# BrickPi_1_6.net
KiCad netlist of a schematic drawn in EAGLE
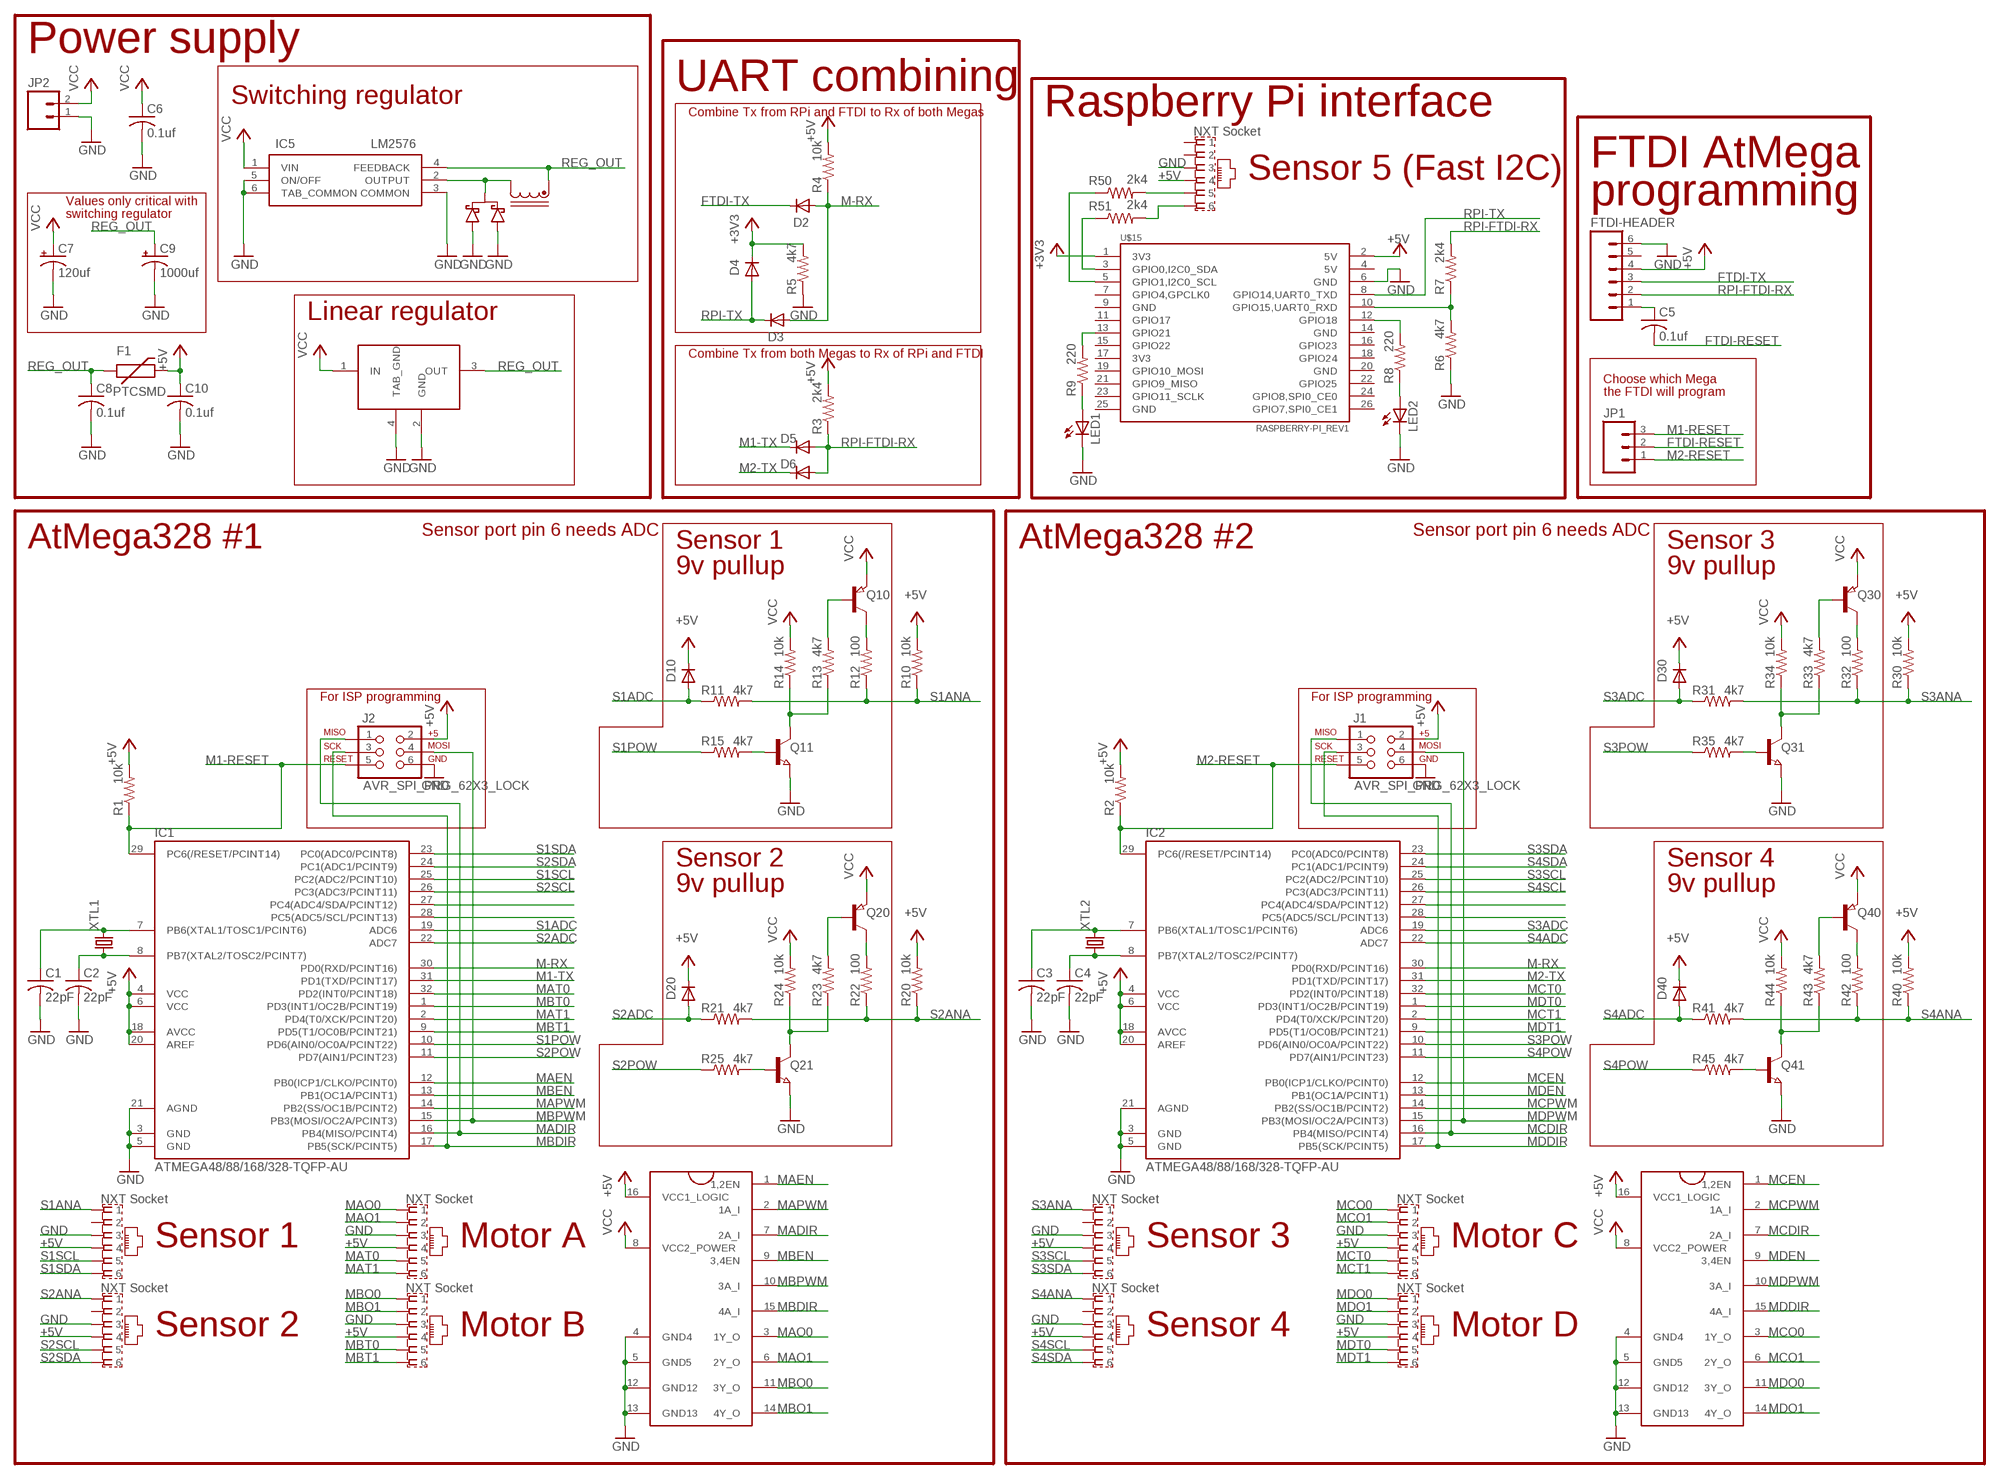
[diagram p0: schematic, sheet 1]

(export (version "E")
  (design (tool "Eeschema 10.0.6"))
  (components
    (comp (ref "C1")
      (value "22pF")
      (footprint "eagle-import:C0805")
      (libsource (lib "eagle-import") (part "C-USC0805"))
    )
    (comp (ref "C2")
      (value "22pF")
      (footprint "eagle-import:C0805")
      (libsource (lib "eagle-import") (part "C-USC0805"))
    )
    (comp (ref "C3")
      (value "22pF")
      (footprint "eagle-import:C0805")
      (libsource (lib "eagle-import") (part "C-USC0805"))
    )
    (comp (ref "C4")
      (value "22pF")
      (footprint "eagle-import:C0805")
      (libsource (lib "eagle-import") (part "C-USC0805"))
    )
    (comp (ref "C5")
      (value "0.1uf")
      (footprint "eagle-import:C0805")
      (libsource (lib "eagle-import") (part "C-USC0805"))
    )
    (comp (ref "C6")
      (value "0.1uf")
      (footprint "eagle-import:C0805")
      (libsource (lib "eagle-import") (part "C-USC0805"))
    )
    (comp (ref "C7")
      (value "120uf")
      (footprint "eagle-import:E2,5-6")
      (libsource (lib "eagle-import") (part "CPOL-USE2.5-6"))
    )
    (comp (ref "C8")
      (value "0.1uf")
      (footprint "eagle-import:C0805")
      (libsource (lib "eagle-import") (part "C-USC0805"))
    )
    (comp (ref "C9")
      (value "1000uf")
      (footprint "eagle-import:E3,5-10")
      (libsource (lib "eagle-import") (part "CPOL-USE3.5-10"))
    )
    (comp (ref "C10")
      (value "0.1uf")
      (footprint "eagle-import:C0805")
      (libsource (lib "eagle-import") (part "C-USC0805"))
    )
    (comp (ref "D1")
      (value "DIODE_SCHOTTKY_VS-6CWQ04FNTRPBF")
      (footprint "eagle-import:DPAK")
      (libsource (lib "eagle-import") (part "DIODE_SCHOTTKY_VS-6CWQ04FNTRPBF"))
    )
    (comp (ref "D2")
      (value "DIODE-SOD80C")
      (footprint "eagle-import:SOD80C")
      (libsource (lib "eagle-import") (part "DIODE-SOD80C"))
    )
    (comp (ref "D3")
      (value "DIODE-SOD80C")
      (footprint "eagle-import:SOD80C")
      (libsource (lib "eagle-import") (part "DIODE-SOD80C"))
    )
    (comp (ref "D4")
      (value "DIODE-SOD80C")
      (footprint "eagle-import:SOD80C")
      (libsource (lib "eagle-import") (part "DIODE-SOD80C"))
    )
    (comp (ref "D5")
      (value "DIODE-SOD80C")
      (footprint "eagle-import:SOD80C")
      (libsource (lib "eagle-import") (part "DIODE-SOD80C"))
    )
    (comp (ref "D6")
      (value "DIODE-SOD80C")
      (footprint "eagle-import:SOD80C")
      (libsource (lib "eagle-import") (part "DIODE-SOD80C"))
    )
    (comp (ref "D10")
      (value "DIODE-SOD80C")
      (footprint "eagle-import:SOD80C")
      (libsource (lib "eagle-import") (part "DIODE-SOD80C"))
    )
    (comp (ref "D20")
      (value "DIODE-SOD80C")
      (footprint "eagle-import:SOD80C")
      (libsource (lib "eagle-import") (part "DIODE-SOD80C"))
    )
    (comp (ref "D30")
      (value "DIODE-SOD80C")
      (footprint "eagle-import:SOD80C")
      (libsource (lib "eagle-import") (part "DIODE-SOD80C"))
    )
    (comp (ref "D40")
      (value "DIODE-SOD80C")
      (footprint "eagle-import:SOD80C")
      (libsource (lib "eagle-import") (part "DIODE-SOD80C"))
    )
    (comp (ref "F1")
      (value "PTCSMD")
      (footprint "eagle-import:PTC-1206")
      (libsource (lib "eagle-import") (part "PTCSMD"))
    )
    (comp (ref "FTDI-HEADER")
      (value "M06LOCK")
      (footprint "eagle-import:1X06_LOCK")
      (libsource (lib "eagle-import") (part "M06LOCK"))
    )
    (comp (ref "IC1")
      (value "ATMEGA48/88/168/328-TQFP-AU")
      (footprint "eagle-import:TQFP32-08")
      (libsource (lib "eagle-import") (part "ATMEGA48/88/168/328-TQFP-AU"))
    )
    (comp (ref "IC2")
      (value "ATMEGA48/88/168/328-TQFP-AU")
      (footprint "eagle-import:TQFP32-08")
      (libsource (lib "eagle-import") (part "ATMEGA48/88/168/328-TQFP-AU"))
    )
    (comp (ref "IC3")
      (value "SN754410")
      (footprint "eagle-import:DIL16-ROUND-HEAT_DIS_SN754410")
      (libsource (lib "eagle-import") (part "SN754410"))
    )
    (comp (ref "IC4")
      (value "SN754410")
      (footprint "eagle-import:DIL16-ROUND-HEAT_DIS_SN754410")
      (libsource (lib "eagle-import") (part "SN754410"))
    )
    (comp (ref "IC5")
      (value "LM2576")
      (footprint "eagle-import:TO220-5-H")
      (libsource (lib "eagle-import") (part "REGULATOR_SWITCHING_LM2575_LM2576"))
    )
    (comp (ref "IC6")
      (value "REGULATOR_5V_TO220-H_7805")
      (footprint "eagle-import:TO220-H")
      (libsource (lib "eagle-import") (part "REGULATOR_5V_TO220-H_7805"))
    )
    (comp (ref "J1")
      (value "AVR_SPI_PRG_62X3_LOCK")
      (footprint "eagle-import:2X3_LOCK")
      (libsource (lib "eagle-import") (part "AVR_SPI_PRG_62X3_LOCK"))
    )
    (comp (ref "J2")
      (value "AVR_SPI_PRG_62X3_LOCK")
      (footprint "eagle-import:2X3_LOCK")
      (libsource (lib "eagle-import") (part "AVR_SPI_PRG_62X3_LOCK"))
    )
    (comp (ref "JP1")
      (value "M03LOCK")
      (footprint "eagle-import:1X03_LOCK")
      (libsource (lib "eagle-import") (part "M03LOCK"))
    )
    (comp (ref "JP2")
      (value "M02LOCK")
      (footprint "eagle-import:1X02_LOCK")
      (libsource (lib "eagle-import") (part "M02LOCK"))
    )
    (comp (ref "LED1")
      (value "LED1206")
      (footprint "eagle-import:LED-1206")
      (libsource (lib "eagle-import") (part "LED1206"))
    )
    (comp (ref "LED2")
      (value "LED1206")
      (footprint "eagle-import:LED-1206")
      (libsource (lib "eagle-import") (part "LED1206"))
    )
    (comp (ref "Q10")
      (value "PNP-TRANSISTOR_SOT23")
      (footprint "eagle-import:SOT23")
      (libsource (lib "eagle-import") (part "PNP-TRANSISTOR_SOT23"))
    )
    (comp (ref "Q11")
      (value "NPN-TRANSISTOR_SOT23")
      (footprint "eagle-import:SOT23")
      (libsource (lib "eagle-import") (part "NPN-TRANSISTOR_SOT23"))
    )
    (comp (ref "Q20")
      (value "PNP-TRANSISTOR_SOT23")
      (footprint "eagle-import:SOT23")
      (libsource (lib "eagle-import") (part "PNP-TRANSISTOR_SOT23"))
    )
    (comp (ref "Q21")
      (value "NPN-TRANSISTOR_SOT23")
      (footprint "eagle-import:SOT23")
      (libsource (lib "eagle-import") (part "NPN-TRANSISTOR_SOT23"))
    )
    (comp (ref "Q30")
      (value "PNP-TRANSISTOR_SOT23")
      (footprint "eagle-import:SOT23")
      (libsource (lib "eagle-import") (part "PNP-TRANSISTOR_SOT23"))
    )
    (comp (ref "Q31")
      (value "NPN-TRANSISTOR_SOT23")
      (footprint "eagle-import:SOT23")
      (libsource (lib "eagle-import") (part "NPN-TRANSISTOR_SOT23"))
    )
    (comp (ref "Q40")
      (value "PNP-TRANSISTOR_SOT23")
      (footprint "eagle-import:SOT23")
      (libsource (lib "eagle-import") (part "PNP-TRANSISTOR_SOT23"))
    )
    (comp (ref "Q41")
      (value "NPN-TRANSISTOR_SOT23")
      (footprint "eagle-import:SOT23")
      (libsource (lib "eagle-import") (part "NPN-TRANSISTOR_SOT23"))
    )
    (comp (ref "R1")
      (value "10k")
      (footprint "eagle-import:0603")
      (libsource (lib "eagle-import") (part "RESISTOR0603-RES"))
    )
    (comp (ref "R2")
      (value "10k")
      (footprint "eagle-import:0603")
      (libsource (lib "eagle-import") (part "RESISTOR0603-RES"))
    )
    (comp (ref "R3")
      (value "2k4")
      (footprint "eagle-import:0603")
      (libsource (lib "eagle-import") (part "RESISTOR0603-RES"))
    )
    (comp (ref "R4")
      (value "10k")
      (footprint "eagle-import:0603")
      (libsource (lib "eagle-import") (part "RESISTOR0603-RES"))
    )
    (comp (ref "R5")
      (value "4k7")
      (footprint "eagle-import:0603")
      (libsource (lib "eagle-import") (part "RESISTOR0603-RES"))
    )
    (comp (ref "R6")
      (value "4k7")
      (footprint "eagle-import:0603")
      (libsource (lib "eagle-import") (part "RESISTOR0603-RES"))
    )
    (comp (ref "R7")
      (value "2k4")
      (footprint "eagle-import:0603")
      (libsource (lib "eagle-import") (part "RESISTOR0603-RES"))
    )
    (comp (ref "R8")
      (value "220")
      (footprint "eagle-import:0603")
      (libsource (lib "eagle-import") (part "RESISTOR0603-RES"))
    )
    (comp (ref "R9")
      (value "220")
      (footprint "eagle-import:0603")
      (libsource (lib "eagle-import") (part "RESISTOR0603-RES"))
    )
    (comp (ref "R10")
      (value "10k")
      (footprint "eagle-import:0603")
      (libsource (lib "eagle-import") (part "RESISTOR0603-RES"))
    )
    (comp (ref "R11")
      (value "4k7")
      (footprint "eagle-import:0603")
      (libsource (lib "eagle-import") (part "RESISTOR0603-RES"))
    )
    (comp (ref "R12")
      (value "100")
      (footprint "eagle-import:0805")
      (libsource (lib "eagle-import") (part "RESISTOR0805-RES"))
    )
    (comp (ref "R13")
      (value "4k7")
      (footprint "eagle-import:0603")
      (libsource (lib "eagle-import") (part "RESISTOR0603-RES"))
    )
    (comp (ref "R14")
      (value "10k")
      (footprint "eagle-import:0603")
      (libsource (lib "eagle-import") (part "RESISTOR0603-RES"))
    )
    (comp (ref "R15")
      (value "4k7")
      (footprint "eagle-import:0603")
      (libsource (lib "eagle-import") (part "RESISTOR0603-RES"))
    )
    (comp (ref "R20")
      (value "10k")
      (footprint "eagle-import:0603")
      (libsource (lib "eagle-import") (part "RESISTOR0603-RES"))
    )
    (comp (ref "R21")
      (value "4k7")
      (footprint "eagle-import:0603")
      (libsource (lib "eagle-import") (part "RESISTOR0603-RES"))
    )
    (comp (ref "R22")
      (value "100")
      (footprint "eagle-import:0805")
      (libsource (lib "eagle-import") (part "RESISTOR0805-RES"))
    )
    (comp (ref "R23")
      (value "4k7")
      (footprint "eagle-import:0603")
      (libsource (lib "eagle-import") (part "RESISTOR0603-RES"))
    )
    (comp (ref "R24")
      (value "10k")
      (footprint "eagle-import:0603")
      (libsource (lib "eagle-import") (part "RESISTOR0603-RES"))
    )
    (comp (ref "R25")
      (value "4k7")
      (footprint "eagle-import:0603")
      (libsource (lib "eagle-import") (part "RESISTOR0603-RES"))
    )
    (comp (ref "R30")
      (value "10k")
      (footprint "eagle-import:0603")
      (libsource (lib "eagle-import") (part "RESISTOR0603-RES"))
    )
    (comp (ref "R31")
      (value "4k7")
      (footprint "eagle-import:0603")
      (libsource (lib "eagle-import") (part "RESISTOR0603-RES"))
    )
    (comp (ref "R32")
      (value "100")
      (footprint "eagle-import:0805")
      (libsource (lib "eagle-import") (part "RESISTOR0805-RES"))
    )
    (comp (ref "R33")
      (value "4k7")
      (footprint "eagle-import:0603")
      (libsource (lib "eagle-import") (part "RESISTOR0603-RES"))
    )
    (comp (ref "R34")
      (value "10k")
      (footprint "eagle-import:0603")
      (libsource (lib "eagle-import") (part "RESISTOR0603-RES"))
    )
    (comp (ref "R35")
      (value "4k7")
      (footprint "eagle-import:0603")
      (libsource (lib "eagle-import") (part "RESISTOR0603-RES"))
    )
    (comp (ref "R40")
      (value "10k")
      (footprint "eagle-import:0603")
      (libsource (lib "eagle-import") (part "RESISTOR0603-RES"))
    )
    (comp (ref "R41")
      (value "4k7")
      (footprint "eagle-import:0603")
      (libsource (lib "eagle-import") (part "RESISTOR0603-RES"))
    )
    (comp (ref "R42")
      (value "100")
      (footprint "eagle-import:0805")
      (libsource (lib "eagle-import") (part "RESISTOR0805-RES"))
    )
    (comp (ref "R43")
      (value "4k7")
      (footprint "eagle-import:0603")
      (libsource (lib "eagle-import") (part "RESISTOR0603-RES"))
    )
    (comp (ref "R44")
      (value "10k")
      (footprint "eagle-import:0603")
      (libsource (lib "eagle-import") (part "RESISTOR0603-RES"))
    )
    (comp (ref "R45")
      (value "4k7")
      (footprint "eagle-import:0603")
      (libsource (lib "eagle-import") (part "RESISTOR0603-RES"))
    )
    (comp (ref "R50")
      (value "2k4")
      (footprint "eagle-import:0603")
      (libsource (lib "eagle-import") (part "RESISTOR0603-RES"))
    )
    (comp (ref "R51")
      (value "2k4")
      (footprint "eagle-import:0603")
      (libsource (lib "eagle-import") (part "RESISTOR0603-RES"))
    )
    (comp (ref "U$3")
      (value "NXT-SOCKETREGULAR")
      (footprint "eagle-import:NXT-SOCKET")
      (libsource (lib "eagle-import") (part "NXT-SOCKETREGULAR"))
    )
    (comp (ref "U$4")
      (value "NXT-SOCKETREGULAR")
      (footprint "eagle-import:NXT-SOCKET")
      (libsource (lib "eagle-import") (part "NXT-SOCKETREGULAR"))
    )
    (comp (ref "U$5")
      (value "NXT-SOCKETREGULAR")
      (footprint "eagle-import:NXT-SOCKET")
      (libsource (lib "eagle-import") (part "NXT-SOCKETREGULAR"))
    )
    (comp (ref "U$7")
      (value "NXT-SOCKETREGULAR")
      (footprint "eagle-import:NXT-SOCKET")
      (libsource (lib "eagle-import") (part "NXT-SOCKETREGULAR"))
    )
    (comp (ref "U$8")
      (value "NXT-SOCKETREGULAR")
      (footprint "eagle-import:NXT-SOCKET")
      (libsource (lib "eagle-import") (part "NXT-SOCKETREGULAR"))
    )
    (comp (ref "U$9")
      (value "NXT-SOCKETREGULAR")
      (footprint "eagle-import:NXT-SOCKET")
      (libsource (lib "eagle-import") (part "NXT-SOCKETREGULAR"))
    )
    (comp (ref "U$10")
      (value "NXT-SOCKETREGULAR")
      (footprint "eagle-import:NXT-SOCKET")
      (libsource (lib "eagle-import") (part "NXT-SOCKETREGULAR"))
    )
    (comp (ref "U$11")
      (value "NXT-SOCKETREGULAR")
      (footprint "eagle-import:NXT-SOCKET")
      (libsource (lib "eagle-import") (part "NXT-SOCKETREGULAR"))
    )
    (comp (ref "U$12")
      (value "NXT-SOCKETREGULAR")
      (footprint "eagle-import:NXT-SOCKET")
      (libsource (lib "eagle-import") (part "NXT-SOCKETREGULAR"))
    )
    (comp (ref "U$14")
      (value "INDUCTOR_PULSE_P0250.XXXNL")
      (footprint "eagle-import:INDUCTOR_PULSE_P0250.XXXNL")
      (libsource (lib "eagle-import") (part "INDUCTOR_PULSE_P0250.XXXNL"))
    )
    (comp (ref "U$15")
      (value "RASPBERRY-PI_REV1")
      (footprint "eagle-import:RASPBERRY-PI_REV1")
      (libsource (lib "eagle-import") (part "RASPBERRY-PI_REV1"))
    )
    (comp (ref "XTL1")
      (value "CRYSTALHC49S")
      (footprint "eagle-import:HC49_S")
      (libsource (lib "eagle-import") (part "CRYSTALHC49S"))
    )
    (comp (ref "XTL2")
      (value "CRYSTALHC49S")
      (footprint "eagle-import:HC49_S")
      (libsource (lib "eagle-import") (part "CRYSTALHC49S"))
    )
  )
  (nets
    (net (code "1") (name "+3V3") (class "Default")
      (node (ref "D4") (pin "C") (pinfunction "C_C") (pintype "passive"))
      (node (ref "R5") (pin "2") (pinfunction "2_2") (pintype "passive"))
      (node (ref "U$15") (pin "1") (pinfunction "3V3_1") (pintype "bidirectional"))
    )
    (net (code "2") (name "+5V") (class "Default")
      (node (ref "C10") (pin "1") (pinfunction "1_1") (pintype "passive"))
      (node (ref "D10") (pin "C") (pinfunction "C_C") (pintype "passive"))
      (node (ref "D20") (pin "C") (pinfunction "C_C") (pintype "passive"))
      (node (ref "D30") (pin "C") (pinfunction "C_C") (pintype "passive"))
      (node (ref "D40") (pin "C") (pinfunction "C_C") (pintype "passive"))
      (node (ref "F1") (pin "2") (pinfunction "2_2") (pintype "bidirectional"))
      (node (ref "FTDI-HEADER") (pin "4") (pinfunction "4_4") (pintype "passive"))
      (node (ref "IC1") (pin "18") (pinfunction "AVCC_18") (pintype "passive"))
      (node (ref "IC1") (pin "20") (pinfunction "AREF_20") (pintype "passive"))
      (node (ref "IC1") (pin "4") (pinfunction "VCC_4") (pintype "power_in"))
      (node (ref "IC1") (pin "6") (pinfunction "VCC_6") (pintype "power_in"))
      (node (ref "IC2") (pin "18") (pinfunction "AVCC_18") (pintype "passive"))
      (node (ref "IC2") (pin "20") (pinfunction "AREF_20") (pintype "passive"))
      (node (ref "IC2") (pin "4") (pinfunction "VCC_4") (pintype "power_in"))
      (node (ref "IC2") (pin "6") (pinfunction "VCC_6") (pintype "power_in"))
      (node (ref "IC3") (pin "16") (pinfunction "VCC1_LOGIC_16") (pintype "bidirectional"))
      (node (ref "IC4") (pin "16") (pinfunction "VCC1_LOGIC_16") (pintype "bidirectional"))
      (node (ref "J1") (pin "2") (pinfunction "2_2") (pintype "passive"))
      (node (ref "J2") (pin "2") (pinfunction "2_2") (pintype "passive"))
      (node (ref "R1") (pin "2") (pinfunction "2_2") (pintype "passive"))
      (node (ref "R10") (pin "2") (pinfunction "2_2") (pintype "passive"))
      (node (ref "R2") (pin "2") (pinfunction "2_2") (pintype "passive"))
      (node (ref "R20") (pin "2") (pinfunction "2_2") (pintype "passive"))
      (node (ref "R3") (pin "2") (pinfunction "2_2") (pintype "passive"))
      (node (ref "R30") (pin "2") (pinfunction "2_2") (pintype "passive"))
      (node (ref "R4") (pin "2") (pinfunction "2_2") (pintype "passive"))
      (node (ref "R40") (pin "2") (pinfunction "2_2") (pintype "passive"))
      (node (ref "U$10") (pin "4") (pinfunction "4_4") (pintype "passive"))
      (node (ref "U$11") (pin "4") (pinfunction "4_4") (pintype "passive"))
      (node (ref "U$12") (pin "4") (pinfunction "4_4") (pintype "passive"))
      (node (ref "U$15") (pin "2") (pinfunction "5V_2") (pintype "bidirectional"))
      (node (ref "U$3") (pin "4") (pinfunction "4_4") (pintype "passive"))
      (node (ref "U$4") (pin "4") (pinfunction "4_4") (pintype "passive"))
      (node (ref "U$5") (pin "4") (pinfunction "4_4") (pintype "passive"))
      (node (ref "U$7") (pin "4") (pinfunction "4_4") (pintype "passive"))
      (node (ref "U$8") (pin "4") (pinfunction "4_4") (pintype "passive"))
      (node (ref "U$9") (pin "4") (pinfunction "4_4") (pintype "passive"))
    )
    (net (code "3") (name "/FTDI-RESET") (class "Default")
      (node (ref "C5") (pin "2") (pinfunction "2_2") (pintype "passive"))
      (node (ref "JP1") (pin "2") (pinfunction "2_2") (pintype "passive"))
    )
    (net (code "4") (name "/FTDI-TX") (class "Default")
      (node (ref "D2") (pin "C") (pinfunction "C_C") (pintype "passive"))
      (node (ref "FTDI-HEADER") (pin "3") (pinfunction "3_3") (pintype "passive"))
    )
    (net (code "5") (name "/M-RX") (class "Default")
      (node (ref "D2") (pin "A") (pinfunction "A_A") (pintype "passive"))
      (node (ref "D3") (pin "A") (pinfunction "A_A") (pintype "passive"))
      (node (ref "IC1") (pin "30") (pinfunction "PD0(RXD/PCINT16)_30") (pintype "bidirectional"))
      (node (ref "IC2") (pin "30") (pinfunction "PD0(RXD/PCINT16)_30") (pintype "bidirectional"))
      (node (ref "R4") (pin "1") (pinfunction "1_1") (pintype "passive"))
    )
    (net (code "6") (name "/M1-RESET") (class "Default")
      (node (ref "IC1") (pin "29") (pinfunction "PC6(/RESET/PCINT14)_29") (pintype "bidirectional"))
      (node (ref "J2") (pin "5") (pinfunction "5_5") (pintype "passive"))
      (node (ref "JP1") (pin "3") (pinfunction "3_3") (pintype "passive"))
      (node (ref "R1") (pin "1") (pinfunction "1_1") (pintype "passive"))
    )
    (net (code "7") (name "/M1-TX") (class "Default")
      (node (ref "D5") (pin "C") (pinfunction "C_C") (pintype "passive"))
      (node (ref "IC1") (pin "31") (pinfunction "PD1(TXD/PCINT17)_31") (pintype "bidirectional"))
    )
    (net (code "8") (name "/M2-RESET") (class "Default")
      (node (ref "IC2") (pin "29") (pinfunction "PC6(/RESET/PCINT14)_29") (pintype "bidirectional"))
      (node (ref "J1") (pin "5") (pinfunction "5_5") (pintype "passive"))
      (node (ref "JP1") (pin "1") (pinfunction "1_1") (pintype "passive"))
      (node (ref "R2") (pin "1") (pinfunction "1_1") (pintype "passive"))
    )
    (net (code "9") (name "/M2-TX") (class "Default")
      (node (ref "D6") (pin "C") (pinfunction "C_C") (pintype "passive"))
      (node (ref "IC2") (pin "31") (pinfunction "PD1(TXD/PCINT17)_31") (pintype "bidirectional"))
    )
    (net (code "10") (name "/MADIR") (class "Default")
      (node (ref "IC1") (pin "16") (pinfunction "PB4(MISO/PCINT4)_16") (pintype "bidirectional"))
      (node (ref "IC3") (pin "7") (pinfunction "2A_I_7") (pintype "bidirectional"))
      (node (ref "J2") (pin "1") (pinfunction "1_1") (pintype "passive"))
    )
    (net (code "11") (name "/MAEN") (class "Default")
      (node (ref "IC1") (pin "12") (pinfunction "PB0(ICP1/CLKO/PCINT0)_12") (pintype "bidirectional"))
      (node (ref "IC3") (pin "1") (pinfunction "1,2EN_1") (pintype "bidirectional"))
    )
    (net (code "12") (name "/MAO0") (class "Default")
      (node (ref "IC3") (pin "3") (pinfunction "1Y_O_3") (pintype "bidirectional"))
      (node (ref "U$3") (pin "1") (pinfunction "1_1") (pintype "passive"))
    )
    (net (code "13") (name "/MAO1") (class "Default")
      (node (ref "IC3") (pin "6") (pinfunction "2Y_O_6") (pintype "bidirectional"))
      (node (ref "U$3") (pin "2") (pinfunction "2_2") (pintype "passive"))
    )
    (net (code "14") (name "/MAPWM") (class "Default")
      (node (ref "IC1") (pin "14") (pinfunction "PB2(SS/OC1B/PCINT2)_14") (pintype "bidirectional"))
      (node (ref "IC3") (pin "2") (pinfunction "1A_I_2") (pintype "bidirectional"))
    )
    (net (code "15") (name "/MAT0") (class "Default")
      (node (ref "IC1") (pin "32") (pinfunction "PD2(INT0/PCINT18)_32") (pintype "bidirectional"))
      (node (ref "U$3") (pin "5") (pinfunction "5_5") (pintype "passive"))
    )
    (net (code "16") (name "/MAT1") (class "Default")
      (node (ref "IC1") (pin "2") (pinfunction "PD4(T0/XCK/PCINT20)_2") (pintype "bidirectional"))
      (node (ref "U$3") (pin "6") (pinfunction "6_6") (pintype "passive"))
    )
    (net (code "17") (name "/MBDIR") (class "Default")
      (node (ref "IC1") (pin "17") (pinfunction "PB5(SCK/PCINT5)_17") (pintype "bidirectional"))
      (node (ref "IC3") (pin "15") (pinfunction "4A_I_15") (pintype "bidirectional"))
      (node (ref "J2") (pin "3") (pinfunction "3_3") (pintype "passive"))
    )
    (net (code "18") (name "/MBEN") (class "Default")
      (node (ref "IC1") (pin "13") (pinfunction "PB1(OC1A/PCINT1)_13") (pintype "bidirectional"))
      (node (ref "IC3") (pin "9") (pinfunction "3,4EN_9") (pintype "bidirectional"))
    )
    (net (code "19") (name "/MBO0") (class "Default")
      (node (ref "IC3") (pin "11") (pinfunction "3Y_O_11") (pintype "bidirectional"))
      (node (ref "U$4") (pin "1") (pinfunction "1_1") (pintype "passive"))
    )
    (net (code "20") (name "/MBO1") (class "Default")
      (node (ref "IC3") (pin "14") (pinfunction "4Y_O_14") (pintype "bidirectional"))
      (node (ref "U$4") (pin "2") (pinfunction "2_2") (pintype "passive"))
    )
    (net (code "21") (name "/MBPWM") (class "Default")
      (node (ref "IC1") (pin "15") (pinfunction "PB3(MOSI/OC2A/PCINT3)_15") (pintype "bidirectional"))
      (node (ref "IC3") (pin "10") (pinfunction "3A_I_10") (pintype "bidirectional"))
      (node (ref "J2") (pin "4") (pinfunction "4_4") (pintype "passive"))
    )
    (net (code "22") (name "/MBT0") (class "Default")
      (node (ref "IC1") (pin "1") (pinfunction "PD3(INT1/OC2B/PCINT19)_1") (pintype "bidirectional"))
      (node (ref "U$4") (pin "5") (pinfunction "5_5") (pintype "passive"))
    )
    (net (code "23") (name "/MBT1") (class "Default")
      (node (ref "IC1") (pin "9") (pinfunction "PD5(T1/OC0B/PCINT21)_9") (pintype "bidirectional"))
      (node (ref "U$4") (pin "6") (pinfunction "6_6") (pintype "passive"))
    )
    (net (code "24") (name "/MCDIR") (class "Default")
      (node (ref "IC2") (pin "16") (pinfunction "PB4(MISO/PCINT4)_16") (pintype "bidirectional"))
      (node (ref "IC4") (pin "7") (pinfunction "2A_I_7") (pintype "bidirectional"))
      (node (ref "J1") (pin "1") (pinfunction "1_1") (pintype "passive"))
    )
    (net (code "25") (name "/MCEN") (class "Default")
      (node (ref "IC2") (pin "12") (pinfunction "PB0(ICP1/CLKO/PCINT0)_12") (pintype "bidirectional"))
      (node (ref "IC4") (pin "1") (pinfunction "1,2EN_1") (pintype "bidirectional"))
    )
    (net (code "26") (name "/MCO0") (class "Default")
      (node (ref "IC4") (pin "3") (pinfunction "1Y_O_3") (pintype "bidirectional"))
      (node (ref "U$5") (pin "1") (pinfunction "1_1") (pintype "passive"))
    )
    (net (code "27") (name "/MCO1") (class "Default")
      (node (ref "IC4") (pin "6") (pinfunction "2Y_O_6") (pintype "bidirectional"))
      (node (ref "U$5") (pin "2") (pinfunction "2_2") (pintype "passive"))
    )
    (net (code "28") (name "/MCPWM") (class "Default")
      (node (ref "IC2") (pin "14") (pinfunction "PB2(SS/OC1B/PCINT2)_14") (pintype "bidirectional"))
      (node (ref "IC4") (pin "2") (pinfunction "1A_I_2") (pintype "bidirectional"))
    )
    (net (code "29") (name "/MCT0") (class "Default")
      (node (ref "IC2") (pin "32") (pinfunction "PD2(INT0/PCINT18)_32") (pintype "bidirectional"))
      (node (ref "U$5") (pin "5") (pinfunction "5_5") (pintype "passive"))
    )
    (net (code "30") (name "/MCT1") (class "Default")
      (node (ref "IC2") (pin "2") (pinfunction "PD4(T0/XCK/PCINT20)_2") (pintype "bidirectional"))
      (node (ref "U$5") (pin "6") (pinfunction "6_6") (pintype "passive"))
    )
    (net (code "31") (name "/MDDIR") (class "Default")
      (node (ref "IC2") (pin "17") (pinfunction "PB5(SCK/PCINT5)_17") (pintype "bidirectional"))
      (node (ref "IC4") (pin "15") (pinfunction "4A_I_15") (pintype "bidirectional"))
      (node (ref "J1") (pin "3") (pinfunction "3_3") (pintype "passive"))
    )
    (net (code "32") (name "/MDEN") (class "Default")
      (node (ref "IC2") (pin "13") (pinfunction "PB1(OC1A/PCINT1)_13") (pintype "bidirectional"))
      (node (ref "IC4") (pin "9") (pinfunction "3,4EN_9") (pintype "bidirectional"))
    )
    (net (code "33") (name "/MDO0") (class "Default")
      (node (ref "IC4") (pin "11") (pinfunction "3Y_O_11") (pintype "bidirectional"))
      (node (ref "U$7") (pin "1") (pinfunction "1_1") (pintype "passive"))
    )
    (net (code "34") (name "/MDO1") (class "Default")
      (node (ref "IC4") (pin "14") (pinfunction "4Y_O_14") (pintype "bidirectional"))
      (node (ref "U$7") (pin "2") (pinfunction "2_2") (pintype "passive"))
    )
    (net (code "35") (name "/MDPWM") (class "Default")
      (node (ref "IC2") (pin "15") (pinfunction "PB3(MOSI/OC2A/PCINT3)_15") (pintype "bidirectional"))
      (node (ref "IC4") (pin "10") (pinfunction "3A_I_10") (pintype "bidirectional"))
      (node (ref "J1") (pin "4") (pinfunction "4_4") (pintype "passive"))
    )
    (net (code "36") (name "/MDT0") (class "Default")
      (node (ref "IC2") (pin "1") (pinfunction "PD3(INT1/OC2B/PCINT19)_1") (pintype "bidirectional"))
      (node (ref "U$7") (pin "5") (pinfunction "5_5") (pintype "passive"))
    )
    (net (code "37") (name "/MDT1") (class "Default")
      (node (ref "IC2") (pin "9") (pinfunction "PD5(T1/OC0B/PCINT21)_9") (pintype "bidirectional"))
      (node (ref "U$7") (pin "6") (pinfunction "6_6") (pintype "passive"))
    )
    (net (code "38") (name "/REG_OUT") (class "Default")
      (node (ref "C8") (pin "1") (pinfunction "1_1") (pintype "passive"))
      (node (ref "C9") (pin "+") (pinfunction "+_+") (pintype "passive"))
      (node (ref "F1") (pin "1") (pinfunction "1_1") (pintype "bidirectional"))
      (node (ref "IC5") (pin "4") (pinfunction "FEEDBACK_4") (pintype "bidirectional"))
      (node (ref "IC6") (pin "3") (pinfunction "OUT_3") (pintype "bidirectional"))
      (node (ref "U$14") (pin "P$1") (pinfunction "P$1_P$1") (pintype "bidirectional"))
    )
    (net (code "39") (name "/RPI-FTDI-RX") (class "Default")
      (node (ref "D5") (pin "A") (pinfunction "A_A") (pintype "passive"))
      (node (ref "D6") (pin "A") (pinfunction "A_A") (pintype "passive"))
      (node (ref "FTDI-HEADER") (pin "2") (pinfunction "2_2") (pintype "passive"))
      (node (ref "R3") (pin "1") (pinfunction "1_1") (pintype "passive"))
      (node (ref "R7") (pin "2") (pinfunction "2_2") (pintype "passive"))
    )
    (net (code "40") (name "/RPI-TX") (class "Default")
      (node (ref "D3") (pin "C") (pinfunction "C_C") (pintype "passive"))
      (node (ref "D4") (pin "A") (pinfunction "A_A") (pintype "passive"))
      (node (ref "U$15") (pin "8") (pinfunction "GPIO14,UART0_TXD_8") (pintype "bidirectional"))
    )
    (net (code "41") (name "/S1ADC") (class "Default")
      (node (ref "D10") (pin "A") (pinfunction "A_A") (pintype "passive"))
      (node (ref "IC1") (pin "19") (pinfunction "ADC6_19") (pintype "passive"))
      (node (ref "R11") (pin "1") (pinfunction "1_1") (pintype "passive"))
    )
    (net (code "42") (name "/S1ANA") (class "Default")
      (node (ref "R10") (pin "1") (pinfunction "1_1") (pintype "passive"))
      (node (ref "R11") (pin "2") (pinfunction "2_2") (pintype "passive"))
      (node (ref "R12") (pin "1") (pinfunction "1_1") (pintype "passive"))
      (node (ref "U$8") (pin "1") (pinfunction "1_1") (pintype "passive"))
    )
    (net (code "43") (name "/S1POW") (class "Default")
      (node (ref "IC1") (pin "10") (pinfunction "PD6(AIN0/OC0A/PCINT22)_10") (pintype "bidirectional"))
      (node (ref "R15") (pin "1") (pinfunction "1_1") (pintype "passive"))
    )
    (net (code "44") (name "/S1SCL") (class "Default")
      (node (ref "IC1") (pin "25") (pinfunction "PC2(ADC2/PCINT10)_25") (pintype "bidirectional"))
      (node (ref "U$8") (pin "5") (pinfunction "5_5") (pintype "passive"))
    )
    (net (code "45") (name "/S1SDA") (class "Default")
      (node (ref "IC1") (pin "23") (pinfunction "PC0(ADC0/PCINT8)_23") (pintype "bidirectional"))
      (node (ref "U$8") (pin "6") (pinfunction "6_6") (pintype "passive"))
    )
    (net (code "46") (name "/S2ADC") (class "Default")
      (node (ref "D20") (pin "A") (pinfunction "A_A") (pintype "passive"))
      (node (ref "IC1") (pin "22") (pinfunction "ADC7_22") (pintype "passive"))
      (node (ref "R21") (pin "1") (pinfunction "1_1") (pintype "passive"))
    )
    (net (code "47") (name "/S2ANA") (class "Default")
      (node (ref "R20") (pin "1") (pinfunction "1_1") (pintype "passive"))
      (node (ref "R21") (pin "2") (pinfunction "2_2") (pintype "passive"))
      (node (ref "R22") (pin "1") (pinfunction "1_1") (pintype "passive"))
      (node (ref "U$9") (pin "1") (pinfunction "1_1") (pintype "passive"))
    )
    (net (code "48") (name "/S2POW") (class "Default")
      (node (ref "IC1") (pin "11") (pinfunction "PD7(AIN1/PCINT23)_11") (pintype "bidirectional"))
      (node (ref "R25") (pin "1") (pinfunction "1_1") (pintype "passive"))
    )
    (net (code "49") (name "/S2SCL") (class "Default")
      (node (ref "IC1") (pin "26") (pinfunction "PC3(ADC3/PCINT11)_26") (pintype "bidirectional"))
      (node (ref "U$9") (pin "5") (pinfunction "5_5") (pintype "passive"))
    )
    (net (code "50") (name "/S2SDA") (class "Default")
      (node (ref "IC1") (pin "24") (pinfunction "PC1(ADC1/PCINT9)_24") (pintype "bidirectional"))
      (node (ref "U$9") (pin "6") (pinfunction "6_6") (pintype "passive"))
    )
    (net (code "51") (name "/S3ADC") (class "Default")
      (node (ref "D30") (pin "A") (pinfunction "A_A") (pintype "passive"))
      (node (ref "IC2") (pin "19") (pinfunction "ADC6_19") (pintype "passive"))
      (node (ref "R31") (pin "1") (pinfunction "1_1") (pintype "passive"))
    )
    (net (code "52") (name "/S3ANA") (class "Default")
      (node (ref "R30") (pin "1") (pinfunction "1_1") (pintype "passive"))
      (node (ref "R31") (pin "2") (pinfunction "2_2") (pintype "passive"))
      (node (ref "R32") (pin "1") (pinfunction "1_1") (pintype "passive"))
      (node (ref "U$10") (pin "1") (pinfunction "1_1") (pintype "passive"))
    )
    (net (code "53") (name "/S3POW") (class "Default")
      (node (ref "IC2") (pin "10") (pinfunction "PD6(AIN0/OC0A/PCINT22)_10") (pintype "bidirectional"))
      (node (ref "R35") (pin "1") (pinfunction "1_1") (pintype "passive"))
    )
    (net (code "54") (name "/S3SCL") (class "Default")
      (node (ref "IC2") (pin "25") (pinfunction "PC2(ADC2/PCINT10)_25") (pintype "bidirectional"))
      (node (ref "U$10") (pin "5") (pinfunction "5_5") (pintype "passive"))
    )
    (net (code "55") (name "/S3SDA") (class "Default")
      (node (ref "IC2") (pin "23") (pinfunction "PC0(ADC0/PCINT8)_23") (pintype "bidirectional"))
      (node (ref "U$10") (pin "6") (pinfunction "6_6") (pintype "passive"))
    )
    (net (code "56") (name "/S4ADC") (class "Default")
      (node (ref "D40") (pin "A") (pinfunction "A_A") (pintype "passive"))
      (node (ref "IC2") (pin "22") (pinfunction "ADC7_22") (pintype "passive"))
      (node (ref "R41") (pin "1") (pinfunction "1_1") (pintype "passive"))
    )
    (net (code "57") (name "/S4ANA") (class "Default")
      (node (ref "R40") (pin "1") (pinfunction "1_1") (pintype "passive"))
      (node (ref "R41") (pin "2") (pinfunction "2_2") (pintype "passive"))
      (node (ref "R42") (pin "1") (pinfunction "1_1") (pintype "passive"))
      (node (ref "U$11") (pin "1") (pinfunction "1_1") (pintype "passive"))
    )
    (net (code "58") (name "/S4POW") (class "Default")
      (node (ref "IC2") (pin "11") (pinfunction "PD7(AIN1/PCINT23)_11") (pintype "bidirectional"))
      (node (ref "R45") (pin "1") (pinfunction "1_1") (pintype "passive"))
    )
    (net (code "59") (name "/S4SCL") (class "Default")
      (node (ref "IC2") (pin "26") (pinfunction "PC3(ADC3/PCINT11)_26") (pintype "bidirectional"))
      (node (ref "U$11") (pin "5") (pinfunction "5_5") (pintype "passive"))
    )
    (net (code "60") (name "/S4SDA") (class "Default")
      (node (ref "IC2") (pin "24") (pinfunction "PC1(ADC1/PCINT9)_24") (pintype "bidirectional"))
      (node (ref "U$11") (pin "6") (pinfunction "6_6") (pintype "passive"))
    )
    (net (code "61") (name "GND") (class "Default")
      (node (ref "C1") (pin "2") (pinfunction "2_2") (pintype "passive"))
      (node (ref "C10") (pin "2") (pinfunction "2_2") (pintype "passive"))
      (node (ref "C2") (pin "2") (pinfunction "2_2") (pintype "passive"))
      (node (ref "C3") (pin "2") (pinfunction "2_2") (pintype "passive"))
      (node (ref "C4") (pin "2") (pinfunction "2_2") (pintype "passive"))
      (node (ref "C6") (pin "2") (pinfunction "2_2") (pintype "passive"))
      (node (ref "C7") (pin "-") (pinfunction "-_-") (pintype "passive"))
      (node (ref "C8") (pin "2") (pinfunction "2_2") (pintype "passive"))
      (node (ref "C9") (pin "-") (pinfunction "-_-") (pintype "passive"))
      (node (ref "D1") (pin "1") (pinfunction "P$1_1") (pintype "bidirectional"))
      (node (ref "D1") (pin "3") (pinfunction "P$3_3") (pintype "bidirectional"))
      (node (ref "FTDI-HEADER") (pin "6") (pinfunction "6_6") (pintype "passive"))
      (node (ref "IC1") (pin "21") (pinfunction "AGND_21") (pintype "power_in"))
      (node (ref "IC1") (pin "3") (pinfunction "GND_3") (pintype "power_in"))
      (node (ref "IC1") (pin "5") (pinfunction "GND_5") (pintype "power_in"))
      (node (ref "IC2") (pin "21") (pinfunction "AGND_21") (pintype "power_in"))
      (node (ref "IC2") (pin "3") (pinfunction "GND_3") (pintype "power_in"))
      (node (ref "IC2") (pin "5") (pinfunction "GND_5") (pintype "power_in"))
      (node (ref "IC3") (pin "12") (pinfunction "GND12_12") (pintype "bidirectional"))
      (node (ref "IC3") (pin "13") (pinfunction "GND13_13") (pintype "bidirectional"))
      (node (ref "IC3") (pin "4") (pinfunction "GND4_4") (pintype "bidirectional"))
      (node (ref "IC3") (pin "5") (pinfunction "GND5_5") (pintype "bidirectional"))
      (node (ref "IC4") (pin "12") (pinfunction "GND12_12") (pintype "bidirectional"))
      (node (ref "IC4") (pin "13") (pinfunction "GND13_13") (pintype "bidirectional"))
      (node (ref "IC4") (pin "4") (pinfunction "GND4_4") (pintype "bidirectional"))
      (node (ref "IC4") (pin "5") (pinfunction "GND5_5") (pintype "bidirectional"))
      (node (ref "IC5") (pin "3") (pinfunction "COMMON_3") (pintype "bidirectional"))
      (node (ref "IC5") (pin "5") (pinfunction "ON/OFF_5") (pintype "bidirectional"))
      (node (ref "IC5") (pin "6") (pinfunction "TAB_COMMON_6") (pintype "bidirectional"))
      (node (ref "IC6") (pin "2") (pinfunction "GND_2") (pintype "bidirectional"))
      (node (ref "IC6") (pin "4") (pinfunction "TAB_GND_4") (pintype "bidirectional"))
      (node (ref "J1") (pin "6") (pinfunction "6_6") (pintype "passive"))
      (node (ref "J2") (pin "6") (pinfunction "6_6") (pintype "passive"))
      (node (ref "JP2") (pin "1") (pinfunction "1_1") (pintype "passive"))
      (node (ref "LED1") (pin "C") (pinfunction "C_C") (pintype "passive"))
      (node (ref "LED2") (pin "C") (pinfunction "C_C") (pintype "passive"))
      (node (ref "Q11") (pin "2") (pinfunction "E_2") (pintype "passive"))
      (node (ref "Q21") (pin "2") (pinfunction "E_2") (pintype "passive"))
      (node (ref "Q31") (pin "2") (pinfunction "E_2") (pintype "passive"))
      (node (ref "Q41") (pin "2") (pinfunction "E_2") (pintype "passive"))
      (node (ref "R5") (pin "1") (pinfunction "1_1") (pintype "passive"))
      (node (ref "R6") (pin "1") (pinfunction "1_1") (pintype "passive"))
      (node (ref "U$10") (pin "3") (pinfunction "3_3") (pintype "passive"))
      (node (ref "U$11") (pin "3") (pinfunction "3_3") (pintype "passive"))
      (node (ref "U$12") (pin "3") (pinfunction "3_3") (pintype "passive"))
      (node (ref "U$15") (pin "6") (pinfunction "GND_6") (pintype "bidirectional"))
      (node (ref "U$3") (pin "3") (pinfunction "3_3") (pintype "passive"))
      (node (ref "U$4") (pin "3") (pinfunction "3_3") (pintype "passive"))
      (node (ref "U$5") (pin "3") (pinfunction "3_3") (pintype "passive"))
      (node (ref "U$7") (pin "3") (pinfunction "3_3") (pintype "passive"))
      (node (ref "U$8") (pin "3") (pinfunction "3_3") (pintype "passive"))
      (node (ref "U$9") (pin "3") (pinfunction "3_3") (pintype "passive"))
    )
    (net (code "62") (name "Net-(C5-Pad1)") (class "Default")
      (node (ref "C5") (pin "1") (pinfunction "1_1") (pintype "passive"))
      (node (ref "FTDI-HEADER") (pin "1") (pinfunction "1_1") (pintype "passive"))
    )
    (net (code "63") (name "Net-(D1-P$2)") (class "Default")
      (node (ref "D1") (pin "4") (pinfunction "P$2_4") (pintype "bidirectional"))
      (node (ref "IC5") (pin "2") (pinfunction "OUTPUT_2") (pintype "bidirectional"))
      (node (ref "U$14") (pin "P$2") (pinfunction "P$2_P$2") (pintype "bidirectional"))
    )
    (net (code "64") (name "Net-(IC1-PB6(XTAL1{slash}TOSC1{slash}PCINT6))") (class "Default")
      (node (ref "C1") (pin "1") (pinfunction "1_1") (pintype "passive"))
      (node (ref "IC1") (pin "7") (pinfunction "PB6(XTAL1/TOSC1/PCINT6)_7") (pintype "bidirectional"))
      (node (ref "XTL1") (pin "2") (pinfunction "2_2") (pintype "passive"))
    )
    (net (code "65") (name "Net-(IC1-PB7(XTAL2{slash}TOSC2{slash}PCINT7))") (class "Default")
      (node (ref "C2") (pin "1") (pinfunction "1_1") (pintype "passive"))
      (node (ref "IC1") (pin "8") (pinfunction "PB7(XTAL2/TOSC2/PCINT7)_8") (pintype "bidirectional"))
      (node (ref "XTL1") (pin "1") (pinfunction "1_1") (pintype "passive"))
    )
    (net (code "66") (name "Net-(IC2-PB6(XTAL1{slash}TOSC1{slash}PCINT6))") (class "Default")
      (node (ref "C3") (pin "1") (pinfunction "1_1") (pintype "passive"))
      (node (ref "IC2") (pin "7") (pinfunction "PB6(XTAL1/TOSC1/PCINT6)_7") (pintype "bidirectional"))
      (node (ref "XTL2") (pin "2") (pinfunction "2_2") (pintype "passive"))
    )
    (net (code "67") (name "Net-(IC2-PB7(XTAL2{slash}TOSC2{slash}PCINT7))") (class "Default")
      (node (ref "C4") (pin "1") (pinfunction "1_1") (pintype "passive"))
      (node (ref "IC2") (pin "8") (pinfunction "PB7(XTAL2/TOSC2/PCINT7)_8") (pintype "bidirectional"))
      (node (ref "XTL2") (pin "1") (pinfunction "1_1") (pintype "passive"))
    )
    (net (code "68") (name "Net-(LED1-PadA)") (class "Default")
      (node (ref "LED1") (pin "A") (pinfunction "A_A") (pintype "passive"))
      (node (ref "R9") (pin "1") (pinfunction "1_1") (pintype "passive"))
    )
    (net (code "69") (name "Net-(LED2-PadA)") (class "Default")
      (node (ref "LED2") (pin "A") (pinfunction "A_A") (pintype "passive"))
      (node (ref "R8") (pin "1") (pinfunction "1_1") (pintype "passive"))
    )
    (net (code "70") (name "Net-(Q10-B)") (class "Default")
      (node (ref "Q10") (pin "1") (pinfunction "B_1") (pintype "passive"))
      (node (ref "R13") (pin "2") (pinfunction "2_2") (pintype "passive"))
    )
    (net (code "71") (name "Net-(Q10-C)") (class "Default")
      (node (ref "Q10") (pin "3") (pinfunction "C_3") (pintype "passive"))
      (node (ref "R12") (pin "2") (pinfunction "2_2") (pintype "passive"))
    )
    (net (code "72") (name "Net-(Q11-B)") (class "Default")
      (node (ref "Q11") (pin "1") (pinfunction "B_1") (pintype "passive"))
      (node (ref "R15") (pin "2") (pinfunction "2_2") (pintype "passive"))
    )
    (net (code "73") (name "Net-(Q11-C)") (class "Default")
      (node (ref "Q11") (pin "3") (pinfunction "C_3") (pintype "passive"))
      (node (ref "R13") (pin "1") (pinfunction "1_1") (pintype "passive"))
      (node (ref "R14") (pin "1") (pinfunction "1_1") (pintype "passive"))
    )
    (net (code "74") (name "Net-(Q20-B)") (class "Default")
      (node (ref "Q20") (pin "1") (pinfunction "B_1") (pintype "passive"))
      (node (ref "R23") (pin "2") (pinfunction "2_2") (pintype "passive"))
    )
    (net (code "75") (name "Net-(Q20-C)") (class "Default")
      (node (ref "Q20") (pin "3") (pinfunction "C_3") (pintype "passive"))
      (node (ref "R22") (pin "2") (pinfunction "2_2") (pintype "passive"))
    )
    (net (code "76") (name "Net-(Q21-B)") (class "Default")
      (node (ref "Q21") (pin "1") (pinfunction "B_1") (pintype "passive"))
      (node (ref "R25") (pin "2") (pinfunction "2_2") (pintype "passive"))
    )
    (net (code "77") (name "Net-(Q21-C)") (class "Default")
      (node (ref "Q21") (pin "3") (pinfunction "C_3") (pintype "passive"))
      (node (ref "R23") (pin "1") (pinfunction "1_1") (pintype "passive"))
      (node (ref "R24") (pin "1") (pinfunction "1_1") (pintype "passive"))
    )
    (net (code "78") (name "Net-(Q30-B)") (class "Default")
      (node (ref "Q30") (pin "1") (pinfunction "B_1") (pintype "passive"))
      (node (ref "R33") (pin "2") (pinfunction "2_2") (pintype "passive"))
    )
    (net (code "79") (name "Net-(Q30-C)") (class "Default")
      (node (ref "Q30") (pin "3") (pinfunction "C_3") (pintype "passive"))
      (node (ref "R32") (pin "2") (pinfunction "2_2") (pintype "passive"))
    )
    (net (code "80") (name "Net-(Q31-B)") (class "Default")
      (node (ref "Q31") (pin "1") (pinfunction "B_1") (pintype "passive"))
      (node (ref "R35") (pin "2") (pinfunction "2_2") (pintype "passive"))
    )
    (net (code "81") (name "Net-(Q31-C)") (class "Default")
      (node (ref "Q31") (pin "3") (pinfunction "C_3") (pintype "passive"))
      (node (ref "R33") (pin "1") (pinfunction "1_1") (pintype "passive"))
      (node (ref "R34") (pin "1") (pinfunction "1_1") (pintype "passive"))
    )
    (net (code "82") (name "Net-(Q40-B)") (class "Default")
      (node (ref "Q40") (pin "1") (pinfunction "B_1") (pintype "passive"))
      (node (ref "R43") (pin "2") (pinfunction "2_2") (pintype "passive"))
    )
    (net (code "83") (name "Net-(Q40-C)") (class "Default")
      (node (ref "Q40") (pin "3") (pinfunction "C_3") (pintype "passive"))
      (node (ref "R42") (pin "2") (pinfunction "2_2") (pintype "passive"))
    )
    (net (code "84") (name "Net-(Q41-B)") (class "Default")
      (node (ref "Q41") (pin "1") (pinfunction "B_1") (pintype "passive"))
      (node (ref "R45") (pin "2") (pinfunction "2_2") (pintype "passive"))
    )
    (net (code "85") (name "Net-(Q41-C)") (class "Default")
      (node (ref "Q41") (pin "3") (pinfunction "C_3") (pintype "passive"))
      (node (ref "R43") (pin "1") (pinfunction "1_1") (pintype "passive"))
      (node (ref "R44") (pin "1") (pinfunction "1_1") (pintype "passive"))
    )
    (net (code "86") (name "Net-(R50-Pad2)") (class "Default")
      (node (ref "R50") (pin "2") (pinfunction "2_2") (pintype "passive"))
      (node (ref "U$12") (pin "5") (pinfunction "5_5") (pintype "passive"))
    )
    (net (code "87") (name "Net-(R51-Pad2)") (class "Default")
      (node (ref "R51") (pin "2") (pinfunction "2_2") (pintype "passive"))
      (node (ref "U$12") (pin "6") (pinfunction "6_6") (pintype "passive"))
    )
    (net (code "88") (name "Net-(U$15-GPIO0,I2C0_SDA)") (class "Default")
      (node (ref "R51") (pin "1") (pinfunction "1_1") (pintype "passive"))
      (node (ref "U$15") (pin "3") (pinfunction "GPIO0,I2C0_SDA_3") (pintype "bidirectional"))
    )
    (net (code "89") (name "Net-(U$15-GPIO1,I2C0_SCL)") (class "Default")
      (node (ref "R50") (pin "1") (pinfunction "1_1") (pintype "passive"))
      (node (ref "U$15") (pin "5") (pinfunction "GPIO1,I2C0_SCL_5") (pintype "bidirectional"))
    )
    (net (code "90") (name "Net-(U$15-GPIO15,UART0_RXD)") (class "Default")
      (node (ref "R6") (pin "2") (pinfunction "2_2") (pintype "passive"))
      (node (ref "R7") (pin "1") (pinfunction "1_1") (pintype "passive"))
      (node (ref "U$15") (pin "10") (pinfunction "GPIO15,UART0_RXD_10") (pintype "bidirectional"))
    )
    (net (code "91") (name "Net-(U$15-GPIO18)") (class "Default")
      (node (ref "R8") (pin "2") (pinfunction "2_2") (pintype "passive"))
      (node (ref "U$15") (pin "12") (pinfunction "GPIO18_12") (pintype "bidirectional"))
    )
    (net (code "92") (name "Net-(U$15-GPIO21)") (class "Default")
      (node (ref "R9") (pin "2") (pinfunction "2_2") (pintype "passive"))
      (node (ref "U$15") (pin "13") (pinfunction "GPIO21_13") (pintype "bidirectional"))
    )
    (net (code "93") (name "VCC") (class "Default")
      (node (ref "C6") (pin "1") (pinfunction "1_1") (pintype "passive"))
      (node (ref "C7") (pin "+") (pinfunction "+_+") (pintype "passive"))
      (node (ref "IC3") (pin "8") (pinfunction "VCC2_POWER_8") (pintype "bidirectional"))
      (node (ref "IC4") (pin "8") (pinfunction "VCC2_POWER_8") (pintype "bidirectional"))
      (node (ref "IC5") (pin "1") (pinfunction "VIN_1") (pintype "bidirectional"))
      (node (ref "IC6") (pin "1") (pinfunction "IN_1") (pintype "bidirectional"))
      (node (ref "JP2") (pin "2") (pinfunction "2_2") (pintype "passive"))
      (node (ref "Q10") (pin "2") (pinfunction "E_2") (pintype "passive"))
      (node (ref "Q20") (pin "2") (pinfunction "E_2") (pintype "passive"))
      (node (ref "Q30") (pin "2") (pinfunction "E_2") (pintype "passive"))
      (node (ref "Q40") (pin "2") (pinfunction "E_2") (pintype "passive"))
      (node (ref "R14") (pin "2") (pinfunction "2_2") (pintype "passive"))
      (node (ref "R24") (pin "2") (pinfunction "2_2") (pintype "passive"))
      (node (ref "R34") (pin "2") (pinfunction "2_2") (pintype "passive"))
      (node (ref "R44") (pin "2") (pinfunction "2_2") (pintype "passive"))
    )
    (net (code "94") (name "unconnected-(FTDI-HEADER-Pad5)") (class "Default")
      (node (ref "FTDI-HEADER") (pin "5") (pinfunction "5_5") (pintype "passive"))
    )
    (net (code "95") (name "unconnected-(IC1-PC4(ADC4{slash}SDA{slash}PCINT12)-Pad27)") (class "Default")
      (node (ref "IC1") (pin "27") (pinfunction "PC4(ADC4/SDA/PCINT12)_27") (pintype "bidirectional"))
    )
    (net (code "96") (name "unconnected-(IC1-PC5(ADC5{slash}SCL{slash}PCINT13)-Pad28)") (class "Default")
      (node (ref "IC1") (pin "28") (pinfunction "PC5(ADC5/SCL/PCINT13)_28") (pintype "bidirectional"))
    )
    (net (code "97") (name "unconnected-(IC2-PC4(ADC4{slash}SDA{slash}PCINT12)-Pad27)") (class "Default")
      (node (ref "IC2") (pin "27") (pinfunction "PC4(ADC4/SDA/PCINT12)_27") (pintype "bidirectional"))
    )
    (net (code "98") (name "unconnected-(IC2-PC5(ADC5{slash}SCL{slash}PCINT13)-Pad28)") (class "Default")
      (node (ref "IC2") (pin "28") (pinfunction "PC5(ADC5/SCL/PCINT13)_28") (pintype "bidirectional"))
    )
    (net (code "99") (name "unconnected-(U$8-Pad2)") (class "Default")
      (node (ref "U$8") (pin "2") (pinfunction "2_2") (pintype "passive"))
    )
    (net (code "100") (name "unconnected-(U$9-Pad2)") (class "Default")
      (node (ref "U$9") (pin "2") (pinfunction "2_2") (pintype "passive"))
    )
    (net (code "101") (name "unconnected-(U$10-Pad2)") (class "Default")
      (node (ref "U$10") (pin "2") (pinfunction "2_2") (pintype "passive"))
    )
    (net (code "102") (name "unconnected-(U$11-Pad2)") (class "Default")
      (node (ref "U$11") (pin "2") (pinfunction "2_2") (pintype "passive"))
    )
    (net (code "103") (name "unconnected-(U$12-Pad1)") (class "Default")
      (node (ref "U$12") (pin "1") (pinfunction "1_1") (pintype "passive"))
    )
    (net (code "104") (name "unconnected-(U$12-Pad2)") (class "Default")
      (node (ref "U$12") (pin "2") (pinfunction "2_2") (pintype "passive"))
    )
    (net (code "105") (name "unconnected-(U$15-3V3-Pad17)") (class "Default")
      (node (ref "U$15") (pin "17") (pinfunction "3V3_17") (pintype "bidirectional"))
    )
    (net (code "106") (name "unconnected-(U$15-5V-Pad4)") (class "Default")
      (node (ref "U$15") (pin "4") (pinfunction "5V_4") (pintype "bidirectional"))
    )
    (net (code "107") (name "unconnected-(U$15-GND-Pad9)") (class "Default")
      (node (ref "U$15") (pin "9") (pinfunction "GND_9") (pintype "bidirectional"))
    )
    (net (code "108") (name "unconnected-(U$15-GND-Pad14)") (class "Default")
      (node (ref "U$15") (pin "14") (pinfunction "GND_14") (pintype "bidirectional"))
    )
    (net (code "109") (name "unconnected-(U$15-GND-Pad20)") (class "Default")
      (node (ref "U$15") (pin "20") (pinfunction "GND_20") (pintype "bidirectional"))
    )
    (net (code "110") (name "unconnected-(U$15-GND-Pad25)") (class "Default")
      (node (ref "U$15") (pin "25") (pinfunction "GND_25") (pintype "bidirectional"))
    )
    (net (code "111") (name "unconnected-(U$15-GPIO4,GPCLK0-Pad7)") (class "Default")
      (node (ref "U$15") (pin "7") (pinfunction "GPIO4,GPCLK0_7") (pintype "bidirectional"))
    )
    (net (code "112") (name "unconnected-(U$15-GPIO7,SPI0_CE1-Pad26)") (class "Default")
      (node (ref "U$15") (pin "26") (pinfunction "GPIO7,SPI0_CE1_26") (pintype "bidirectional"))
    )
    (net (code "113") (name "unconnected-(U$15-GPIO8,SPI0_CE0-Pad24)") (class "Default")
      (node (ref "U$15") (pin "24") (pinfunction "GPIO8,SPI0_CE0_24") (pintype "bidirectional"))
    )
    (net (code "114") (name "unconnected-(U$15-GPIO9_MISO-Pad21)") (class "Default")
      (node (ref "U$15") (pin "21") (pinfunction "GPIO9_MISO_21") (pintype "bidirectional"))
    )
    (net (code "115") (name "unconnected-(U$15-GPIO10_MOSI-Pad19)") (class "Default")
      (node (ref "U$15") (pin "19") (pinfunction "GPIO10_MOSI_19") (pintype "bidirectional"))
    )
    (net (code "116") (name "unconnected-(U$15-GPIO11_SCLK-Pad23)") (class "Default")
      (node (ref "U$15") (pin "23") (pinfunction "GPIO11_SCLK_23") (pintype "bidirectional"))
    )
    (net (code "117") (name "unconnected-(U$15-GPIO17-Pad11)") (class "Default")
      (node (ref "U$15") (pin "11") (pinfunction "GPIO17_11") (pintype "bidirectional"))
    )
    (net (code "118") (name "unconnected-(U$15-GPIO22-Pad15)") (class "Default")
      (node (ref "U$15") (pin "15") (pinfunction "GPIO22_15") (pintype "bidirectional"))
    )
    (net (code "119") (name "unconnected-(U$15-GPIO23-Pad16)") (class "Default")
      (node (ref "U$15") (pin "16") (pinfunction "GPIO23_16") (pintype "bidirectional"))
    )
    (net (code "120") (name "unconnected-(U$15-GPIO24-Pad18)") (class "Default")
      (node (ref "U$15") (pin "18") (pinfunction "GPIO24_18") (pintype "bidirectional"))
    )
    (net (code "121") (name "unconnected-(U$15-GPIO25-Pad22)") (class "Default")
      (node (ref "U$15") (pin "22") (pinfunction "GPIO25_22") (pintype "bidirectional"))
    )
  )
)
